# OpenHealth_rj45.net
KiCad netlist of a schematic drawn in EAGLE
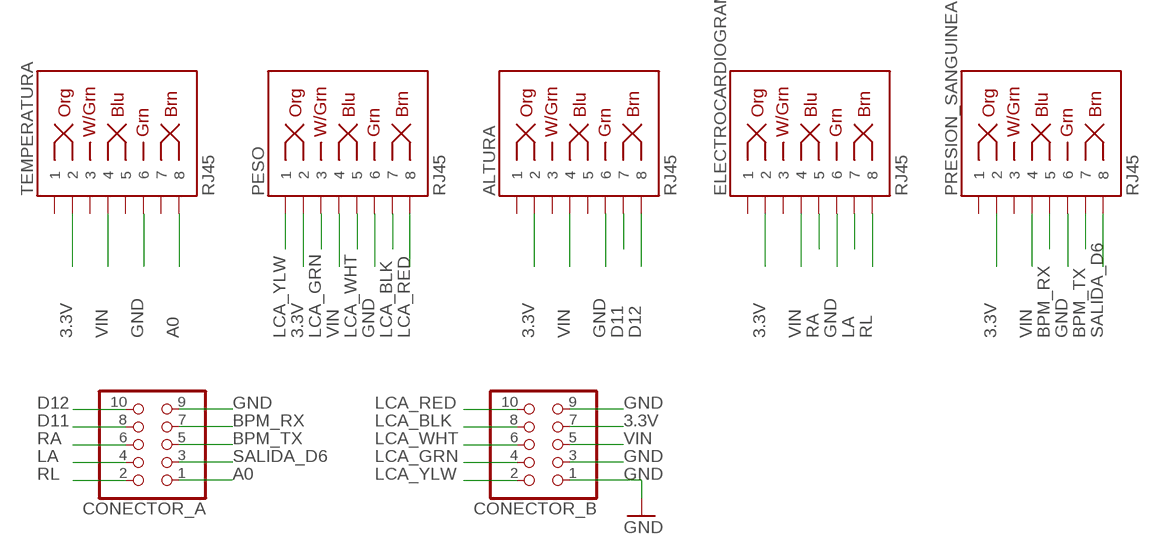
[diagram p0: schematic, sheet 1]

(export (version "E")
  (design (tool "Eeschema 10.0.6"))
  (components
    (comp (ref "ALTURA")
      (value "RJ45")
      (footprint "eagle-import:RJ45-8")
      (libsource (lib "eagle-import") (part "RJ45-8PTH"))
    )
    (comp (ref "CONECTOR_A")
      (value "PINHD-2X5")
      (footprint "eagle-import:2X05")
      (libsource (lib "eagle-import") (part "PINHD-2X5"))
    )
    (comp (ref "CONECTOR_B")
      (value "PINHD-2X5")
      (footprint "eagle-import:2X05")
      (libsource (lib "eagle-import") (part "PINHD-2X5"))
    )
    (comp (ref "ELECTROCARDIOGRAMA")
      (value "RJ45")
      (footprint "eagle-import:RJ45-8")
      (libsource (lib "eagle-import") (part "RJ45-8PTH"))
    )
    (comp (ref "PESO")
      (value "RJ45")
      (footprint "eagle-import:RJ45-8")
      (libsource (lib "eagle-import") (part "RJ45-8PTH"))
    )
    (comp (ref "PRESION_SANGUINEA")
      (value "RJ45")
      (footprint "eagle-import:RJ45-8")
      (libsource (lib "eagle-import") (part "RJ45-8PTH"))
    )
    (comp (ref "TEMPERATURA")
      (value "RJ45")
      (footprint "eagle-import:RJ45-8")
      (libsource (lib "eagle-import") (part "RJ45-8PTH"))
    )
  )
  (nets
    (net (code "1") (name "/3.3V") (class "Default")
      (node (ref "ALTURA") (pin "2") (pinfunction "2_2") (pintype "bidirectional"))
      (node (ref "CONECTOR_B") (pin "7") (pinfunction "7_7") (pintype "passive"))
      (node (ref "ELECTROCARDIOGRAMA") (pin "2") (pinfunction "2_2") (pintype "bidirectional"))
      (node (ref "PESO") (pin "2") (pinfunction "2_2") (pintype "bidirectional"))
      (node (ref "PRESION_SANGUINEA") (pin "2") (pinfunction "2_2") (pintype "bidirectional"))
      (node (ref "TEMPERATURA") (pin "2") (pinfunction "2_2") (pintype "bidirectional"))
    )
    (net (code "2") (name "/A0") (class "Default")
      (node (ref "CONECTOR_A") (pin "1") (pinfunction "1_1") (pintype "passive"))
      (node (ref "TEMPERATURA") (pin "8") (pinfunction "8_8") (pintype "bidirectional"))
    )
    (net (code "3") (name "/BPM_RX") (class "Default")
      (node (ref "CONECTOR_A") (pin "7") (pinfunction "7_7") (pintype "passive"))
      (node (ref "PRESION_SANGUINEA") (pin "5") (pinfunction "5_5") (pintype "bidirectional"))
    )
    (net (code "4") (name "/BPM_TX") (class "Default")
      (node (ref "CONECTOR_A") (pin "5") (pinfunction "5_5") (pintype "passive"))
      (node (ref "PRESION_SANGUINEA") (pin "7") (pinfunction "7_7") (pintype "bidirectional"))
    )
    (net (code "5") (name "/D11") (class "Default")
      (node (ref "ALTURA") (pin "7") (pinfunction "7_7") (pintype "bidirectional"))
      (node (ref "CONECTOR_A") (pin "8") (pinfunction "8_8") (pintype "passive"))
    )
    (net (code "6") (name "/D12") (class "Default")
      (node (ref "ALTURA") (pin "8") (pinfunction "8_8") (pintype "bidirectional"))
      (node (ref "CONECTOR_A") (pin "10") (pinfunction "10_10") (pintype "passive"))
    )
    (net (code "7") (name "/LA") (class "Default")
      (node (ref "CONECTOR_A") (pin "4") (pinfunction "4_4") (pintype "passive"))
      (node (ref "ELECTROCARDIOGRAMA") (pin "7") (pinfunction "7_7") (pintype "bidirectional"))
    )
    (net (code "8") (name "/LCA_BLK") (class "Default")
      (node (ref "CONECTOR_B") (pin "8") (pinfunction "8_8") (pintype "passive"))
      (node (ref "PESO") (pin "7") (pinfunction "7_7") (pintype "bidirectional"))
    )
    (net (code "9") (name "/LCA_GRN") (class "Default")
      (node (ref "CONECTOR_B") (pin "4") (pinfunction "4_4") (pintype "passive"))
      (node (ref "PESO") (pin "3") (pinfunction "3_3") (pintype "bidirectional"))
    )
    (net (code "10") (name "/LCA_RED") (class "Default")
      (node (ref "CONECTOR_B") (pin "10") (pinfunction "10_10") (pintype "passive"))
      (node (ref "PESO") (pin "8") (pinfunction "8_8") (pintype "bidirectional"))
    )
    (net (code "11") (name "/LCA_WHT") (class "Default")
      (node (ref "CONECTOR_B") (pin "6") (pinfunction "6_6") (pintype "passive"))
      (node (ref "PESO") (pin "5") (pinfunction "5_5") (pintype "bidirectional"))
    )
    (net (code "12") (name "/LCA_YLW") (class "Default")
      (node (ref "CONECTOR_B") (pin "2") (pinfunction "2_2") (pintype "passive"))
      (node (ref "PESO") (pin "1") (pinfunction "1_1") (pintype "bidirectional"))
    )
    (net (code "13") (name "/RA") (class "Default")
      (node (ref "CONECTOR_A") (pin "6") (pinfunction "6_6") (pintype "passive"))
      (node (ref "ELECTROCARDIOGRAMA") (pin "5") (pinfunction "5_5") (pintype "bidirectional"))
    )
    (net (code "14") (name "/RL") (class "Default")
      (node (ref "CONECTOR_A") (pin "2") (pinfunction "2_2") (pintype "passive"))
      (node (ref "ELECTROCARDIOGRAMA") (pin "8") (pinfunction "8_8") (pintype "bidirectional"))
    )
    (net (code "15") (name "/SALIDA_D6") (class "Default")
      (node (ref "CONECTOR_A") (pin "3") (pinfunction "3_3") (pintype "passive"))
      (node (ref "PRESION_SANGUINEA") (pin "8") (pinfunction "8_8") (pintype "bidirectional"))
    )
    (net (code "16") (name "/VIN") (class "Default")
      (node (ref "ALTURA") (pin "4") (pinfunction "4_4") (pintype "bidirectional"))
      (node (ref "CONECTOR_B") (pin "5") (pinfunction "5_5") (pintype "passive"))
      (node (ref "ELECTROCARDIOGRAMA") (pin "4") (pinfunction "4_4") (pintype "bidirectional"))
      (node (ref "PESO") (pin "4") (pinfunction "4_4") (pintype "bidirectional"))
      (node (ref "PRESION_SANGUINEA") (pin "4") (pinfunction "4_4") (pintype "bidirectional"))
      (node (ref "TEMPERATURA") (pin "4") (pinfunction "4_4") (pintype "bidirectional"))
    )
    (net (code "17") (name "GND") (class "Default")
      (node (ref "ALTURA") (pin "6") (pinfunction "6_6") (pintype "bidirectional"))
      (node (ref "CONECTOR_A") (pin "9") (pinfunction "9_9") (pintype "passive"))
      (node (ref "CONECTOR_B") (pin "1") (pinfunction "1_1") (pintype "passive"))
      (node (ref "CONECTOR_B") (pin "3") (pinfunction "3_3") (pintype "passive"))
      (node (ref "CONECTOR_B") (pin "9") (pinfunction "9_9") (pintype "passive"))
      (node (ref "ELECTROCARDIOGRAMA") (pin "6") (pinfunction "6_6") (pintype "bidirectional"))
      (node (ref "PESO") (pin "6") (pinfunction "6_6") (pintype "bidirectional"))
      (node (ref "PRESION_SANGUINEA") (pin "6") (pinfunction "6_6") (pintype "bidirectional"))
      (node (ref "TEMPERATURA") (pin "6") (pinfunction "6_6") (pintype "bidirectional"))
    )
    (net (code "18") (name "unconnected-(ALTURA-Pad1)") (class "Default")
      (node (ref "ALTURA") (pin "1") (pinfunction "1_1") (pintype "bidirectional"))
    )
    (net (code "19") (name "unconnected-(ALTURA-Pad3)") (class "Default")
      (node (ref "ALTURA") (pin "3") (pinfunction "3_3") (pintype "bidirectional"))
    )
    (net (code "20") (name "unconnected-(ALTURA-Pad5)") (class "Default")
      (node (ref "ALTURA") (pin "5") (pinfunction "5_5") (pintype "bidirectional"))
    )
    (net (code "21") (name "unconnected-(ELECTROCARDIOGRAMA-Pad1)") (class "Default")
      (node (ref "ELECTROCARDIOGRAMA") (pin "1") (pinfunction "1_1") (pintype "bidirectional"))
    )
    (net (code "22") (name "unconnected-(ELECTROCARDIOGRAMA-Pad3)") (class "Default")
      (node (ref "ELECTROCARDIOGRAMA") (pin "3") (pinfunction "3_3") (pintype "bidirectional"))
    )
    (net (code "23") (name "unconnected-(PRESION_SANGUINEA-Pad1)") (class "Default")
      (node (ref "PRESION_SANGUINEA") (pin "1") (pinfunction "1_1") (pintype "bidirectional"))
    )
    (net (code "24") (name "unconnected-(PRESION_SANGUINEA-Pad3)") (class "Default")
      (node (ref "PRESION_SANGUINEA") (pin "3") (pinfunction "3_3") (pintype "bidirectional"))
    )
    (net (code "25") (name "unconnected-(TEMPERATURA-Pad1)") (class "Default")
      (node (ref "TEMPERATURA") (pin "1") (pinfunction "1_1") (pintype "bidirectional"))
    )
    (net (code "26") (name "unconnected-(TEMPERATURA-Pad3)") (class "Default")
      (node (ref "TEMPERATURA") (pin "3") (pinfunction "3_3") (pintype "bidirectional"))
    )
    (net (code "27") (name "unconnected-(TEMPERATURA-Pad5)") (class "Default")
      (node (ref "TEMPERATURA") (pin "5") (pinfunction "5_5") (pintype "bidirectional"))
    )
    (net (code "28") (name "unconnected-(TEMPERATURA-Pad7)") (class "Default")
      (node (ref "TEMPERATURA") (pin "7") (pinfunction "7_7") (pintype "bidirectional"))
    )
  )
)
